# Adapter-CMRI8-line-stall-motor-adapter.net
KiCad netlist of a schematic drawn in EAGLE
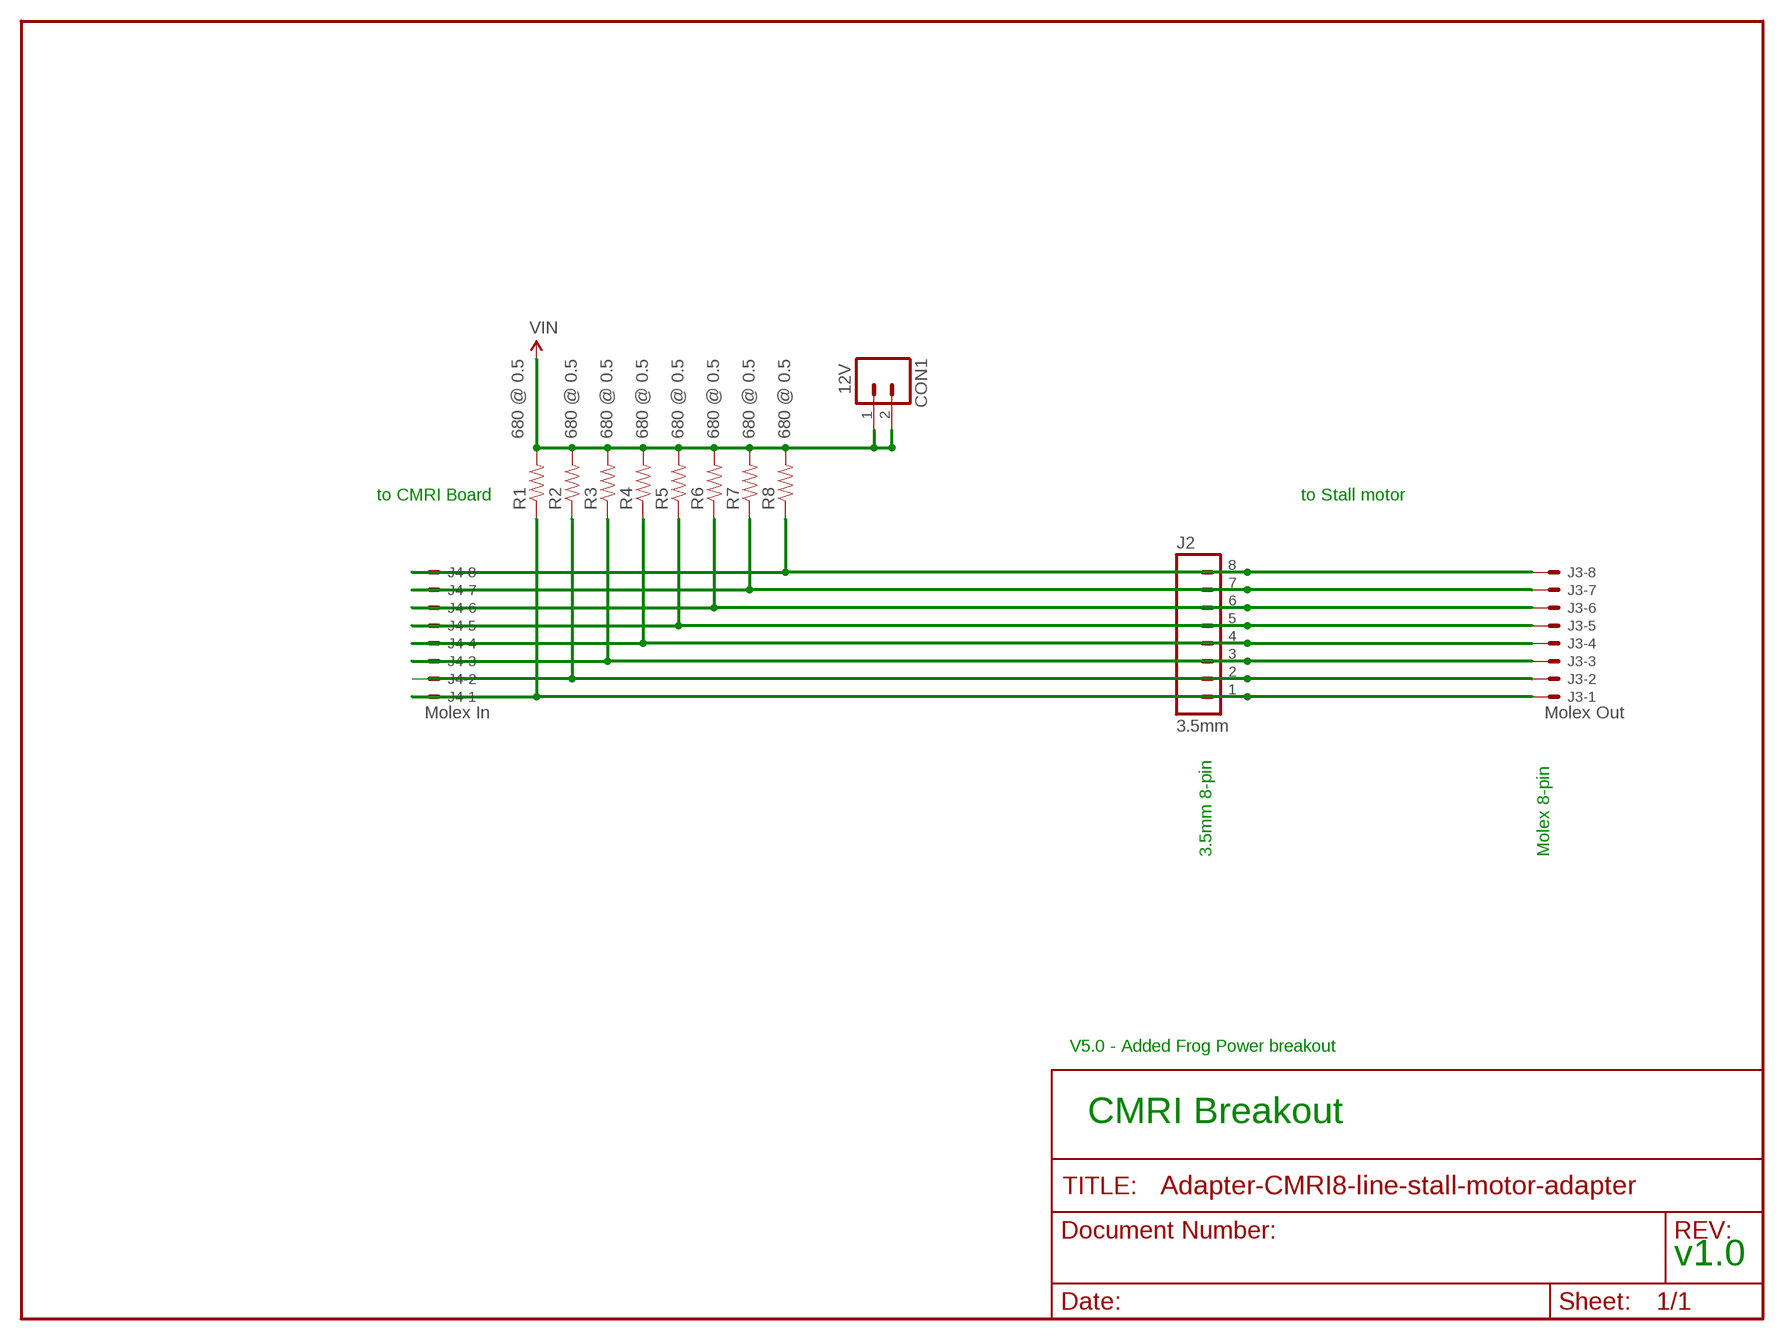
[diagram p0: schematic, sheet 1]

(export (version "E")
  (design (tool "Eeschema 10.0.6"))
  (components
    (comp (ref "CON1")
      (value "12V")
      (footprint "eagle-import:SCREWTERMINAL-3.5MM-2_LOCK")
      (libsource (lib "eagle-import") (part "CONNECTOR-M023.5MM-LOCK"))
    )
    (comp (ref "J2")
      (value "3.5mm")
      (footprint "eagle-import:SCREWTERMINAL-3.5MM-8")
      (libsource (lib "eagle-import") (part "CONNECTOR-M083.5MM-8"))
    )
    (comp (ref "J3")
      (value "Molex Out")
      (footprint "eagle-import:KK-156-8-F")
      (libsource (lib "eagle-import") (part "KK-156-8F"))
    )
    (comp (ref "J4")
      (value "Molex In")
      (footprint "eagle-import:KK-156-8-F")
      (libsource (lib "eagle-import") (part "KK-156-8F"))
    )
    (comp (ref "R1")
      (value "680 @ 0.5")
      (footprint "eagle-import:AXIAL-0.5")
      (libsource (lib "eagle-import") (part "RESISTORPTH-1/2W"))
    )
    (comp (ref "R2")
      (value "680 @ 0.5")
      (footprint "eagle-import:AXIAL-0.5")
      (libsource (lib "eagle-import") (part "RESISTORPTH-1/2W"))
    )
    (comp (ref "R3")
      (value "680 @ 0.5")
      (footprint "eagle-import:AXIAL-0.5")
      (libsource (lib "eagle-import") (part "RESISTORPTH-1/2W"))
    )
    (comp (ref "R4")
      (value "680 @ 0.5")
      (footprint "eagle-import:AXIAL-0.5")
      (libsource (lib "eagle-import") (part "RESISTORPTH-1/2W"))
    )
    (comp (ref "R5")
      (value "680 @ 0.5")
      (footprint "eagle-import:AXIAL-0.5")
      (libsource (lib "eagle-import") (part "RESISTORPTH-1/2W"))
    )
    (comp (ref "R6")
      (value "680 @ 0.5")
      (footprint "eagle-import:AXIAL-0.5")
      (libsource (lib "eagle-import") (part "RESISTORPTH-1/2W"))
    )
    (comp (ref "R7")
      (value "680 @ 0.5")
      (footprint "eagle-import:AXIAL-0.5")
      (libsource (lib "eagle-import") (part "RESISTORPTH-1/2W"))
    )
    (comp (ref "R8")
      (value "680 @ 0.5")
      (footprint "eagle-import:AXIAL-0.5")
      (libsource (lib "eagle-import") (part "RESISTORPTH-1/2W"))
    )
  )
  (nets
    (net (code "1") (name "Net-(J3A-S)") (class "Default")
      (node (ref "J2") (pin "1") (pinfunction "1_1") (pintype "passive"))
      (node (ref "J3") (pin "1") (pinfunction "S_1") (pintype "passive"))
      (node (ref "J4") (pin "1") (pinfunction "S_1") (pintype "passive"))
      (node (ref "R1") (pin "P$1") (pinfunction "1_P$1") (pintype "passive"))
    )
    (net (code "2") (name "Net-(J3B-S)") (class "Default")
      (node (ref "J2") (pin "2") (pinfunction "2_2") (pintype "passive"))
      (node (ref "J3") (pin "2") (pinfunction "S_2") (pintype "passive"))
      (node (ref "J4") (pin "2") (pinfunction "S_2") (pintype "passive"))
      (node (ref "R2") (pin "P$1") (pinfunction "1_P$1") (pintype "passive"))
    )
    (net (code "3") (name "Net-(J3C-S)") (class "Default")
      (node (ref "J2") (pin "3") (pinfunction "3_3") (pintype "passive"))
      (node (ref "J3") (pin "3") (pinfunction "S_3") (pintype "passive"))
      (node (ref "J4") (pin "3") (pinfunction "S_3") (pintype "passive"))
      (node (ref "R3") (pin "P$1") (pinfunction "1_P$1") (pintype "passive"))
    )
    (net (code "4") (name "Net-(J3D-S)") (class "Default")
      (node (ref "J2") (pin "4") (pinfunction "4_4") (pintype "passive"))
      (node (ref "J3") (pin "4") (pinfunction "S_4") (pintype "passive"))
      (node (ref "J4") (pin "4") (pinfunction "S_4") (pintype "passive"))
      (node (ref "R4") (pin "P$1") (pinfunction "1_P$1") (pintype "passive"))
    )
    (net (code "5") (name "Net-(J3E-S)") (class "Default")
      (node (ref "J2") (pin "5") (pinfunction "5_5") (pintype "passive"))
      (node (ref "J3") (pin "5") (pinfunction "S_5") (pintype "passive"))
      (node (ref "J4") (pin "5") (pinfunction "S_5") (pintype "passive"))
      (node (ref "R5") (pin "P$1") (pinfunction "1_P$1") (pintype "passive"))
    )
    (net (code "6") (name "Net-(J3F-S)") (class "Default")
      (node (ref "J2") (pin "6") (pinfunction "6_6") (pintype "passive"))
      (node (ref "J3") (pin "6") (pinfunction "S_6") (pintype "passive"))
      (node (ref "J4") (pin "6") (pinfunction "S_6") (pintype "passive"))
      (node (ref "R6") (pin "P$1") (pinfunction "1_P$1") (pintype "passive"))
    )
    (net (code "7") (name "Net-(J3G-S)") (class "Default")
      (node (ref "J2") (pin "7") (pinfunction "7_7") (pintype "passive"))
      (node (ref "J3") (pin "7") (pinfunction "S_7") (pintype "passive"))
      (node (ref "J4") (pin "7") (pinfunction "S_7") (pintype "passive"))
      (node (ref "R7") (pin "P$1") (pinfunction "1_P$1") (pintype "passive"))
    )
    (net (code "8") (name "Net-(J3H-S)") (class "Default")
      (node (ref "J2") (pin "8") (pinfunction "8_8") (pintype "passive"))
      (node (ref "J3") (pin "8") (pinfunction "S_8") (pintype "passive"))
      (node (ref "J4") (pin "8") (pinfunction "S_8") (pintype "passive"))
      (node (ref "R8") (pin "P$1") (pinfunction "1_P$1") (pintype "passive"))
    )
    (net (code "9") (name "VIN") (class "Default")
      (node (ref "CON1") (pin "1") (pinfunction "A_1") (pintype "passive"))
      (node (ref "CON1") (pin "2") (pinfunction "B_2") (pintype "passive"))
      (node (ref "R1") (pin "P$2") (pinfunction "2_P$2") (pintype "passive"))
      (node (ref "R2") (pin "P$2") (pinfunction "2_P$2") (pintype "passive"))
      (node (ref "R3") (pin "P$2") (pinfunction "2_P$2") (pintype "passive"))
      (node (ref "R4") (pin "P$2") (pinfunction "2_P$2") (pintype "passive"))
      (node (ref "R5") (pin "P$2") (pinfunction "2_P$2") (pintype "passive"))
      (node (ref "R6") (pin "P$2") (pinfunction "2_P$2") (pintype "passive"))
      (node (ref "R7") (pin "P$2") (pinfunction "2_P$2") (pintype "passive"))
      (node (ref "R8") (pin "P$2") (pinfunction "2_P$2") (pintype "passive"))
    )
  )
)
